# board.net
KiCad netlist of a schematic drawn in EAGLE
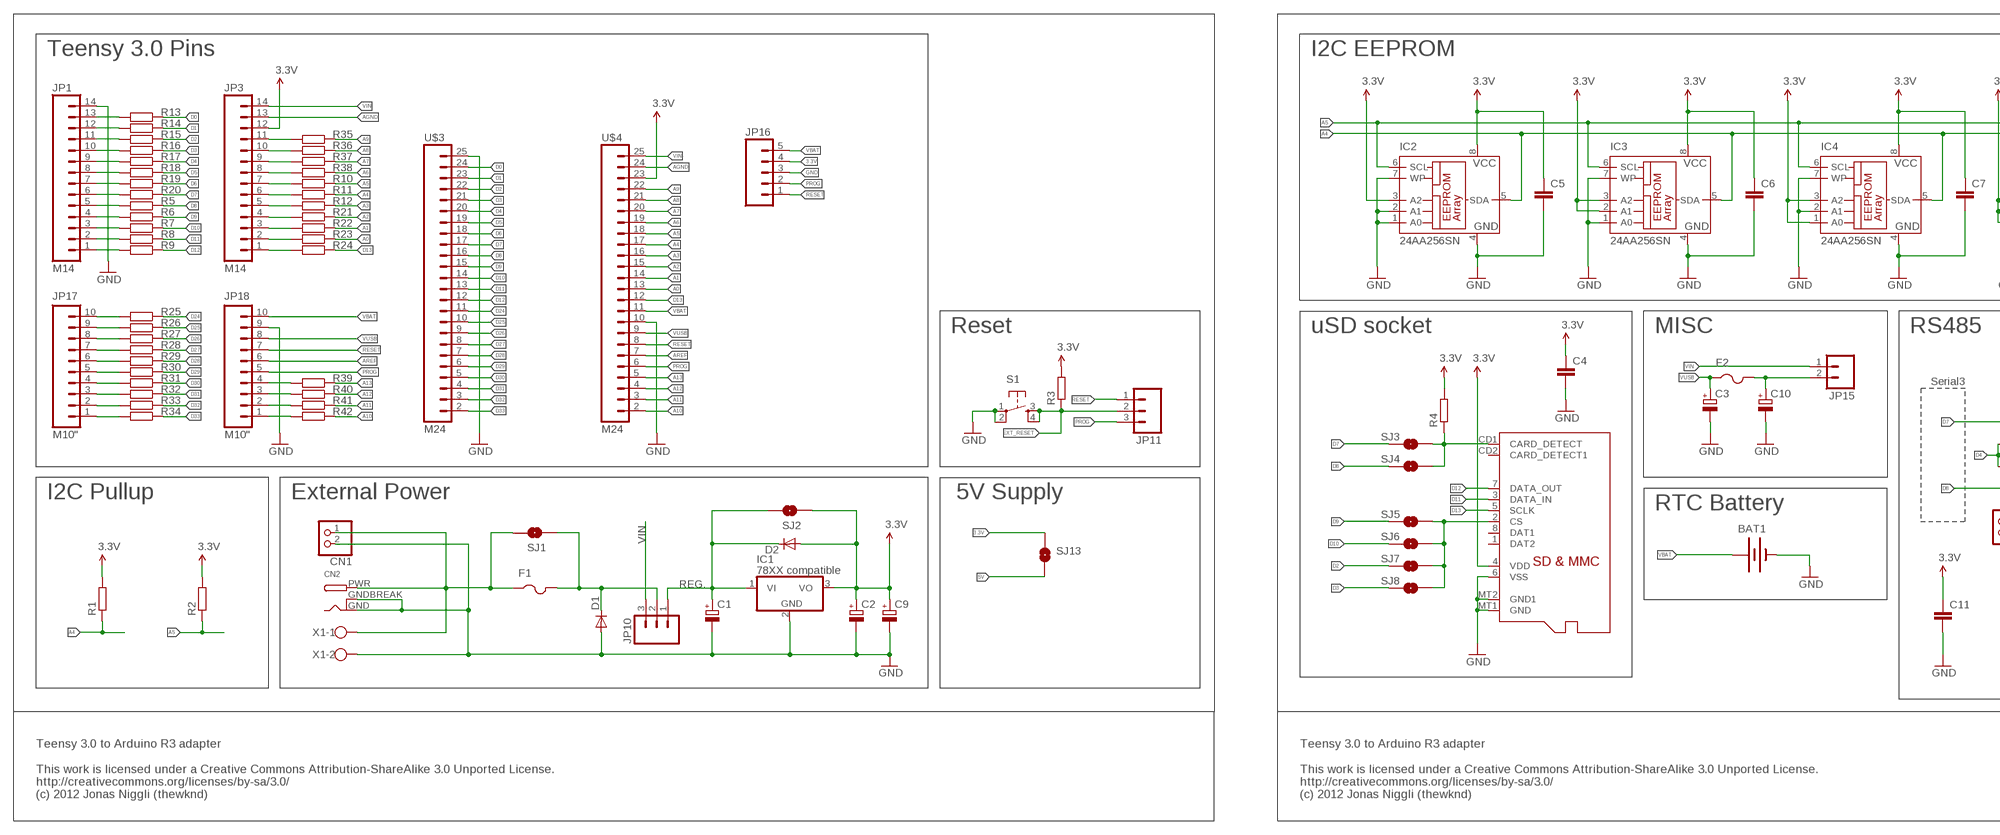
[diagram p0: schematic, sheet 1, part 1 of 2]
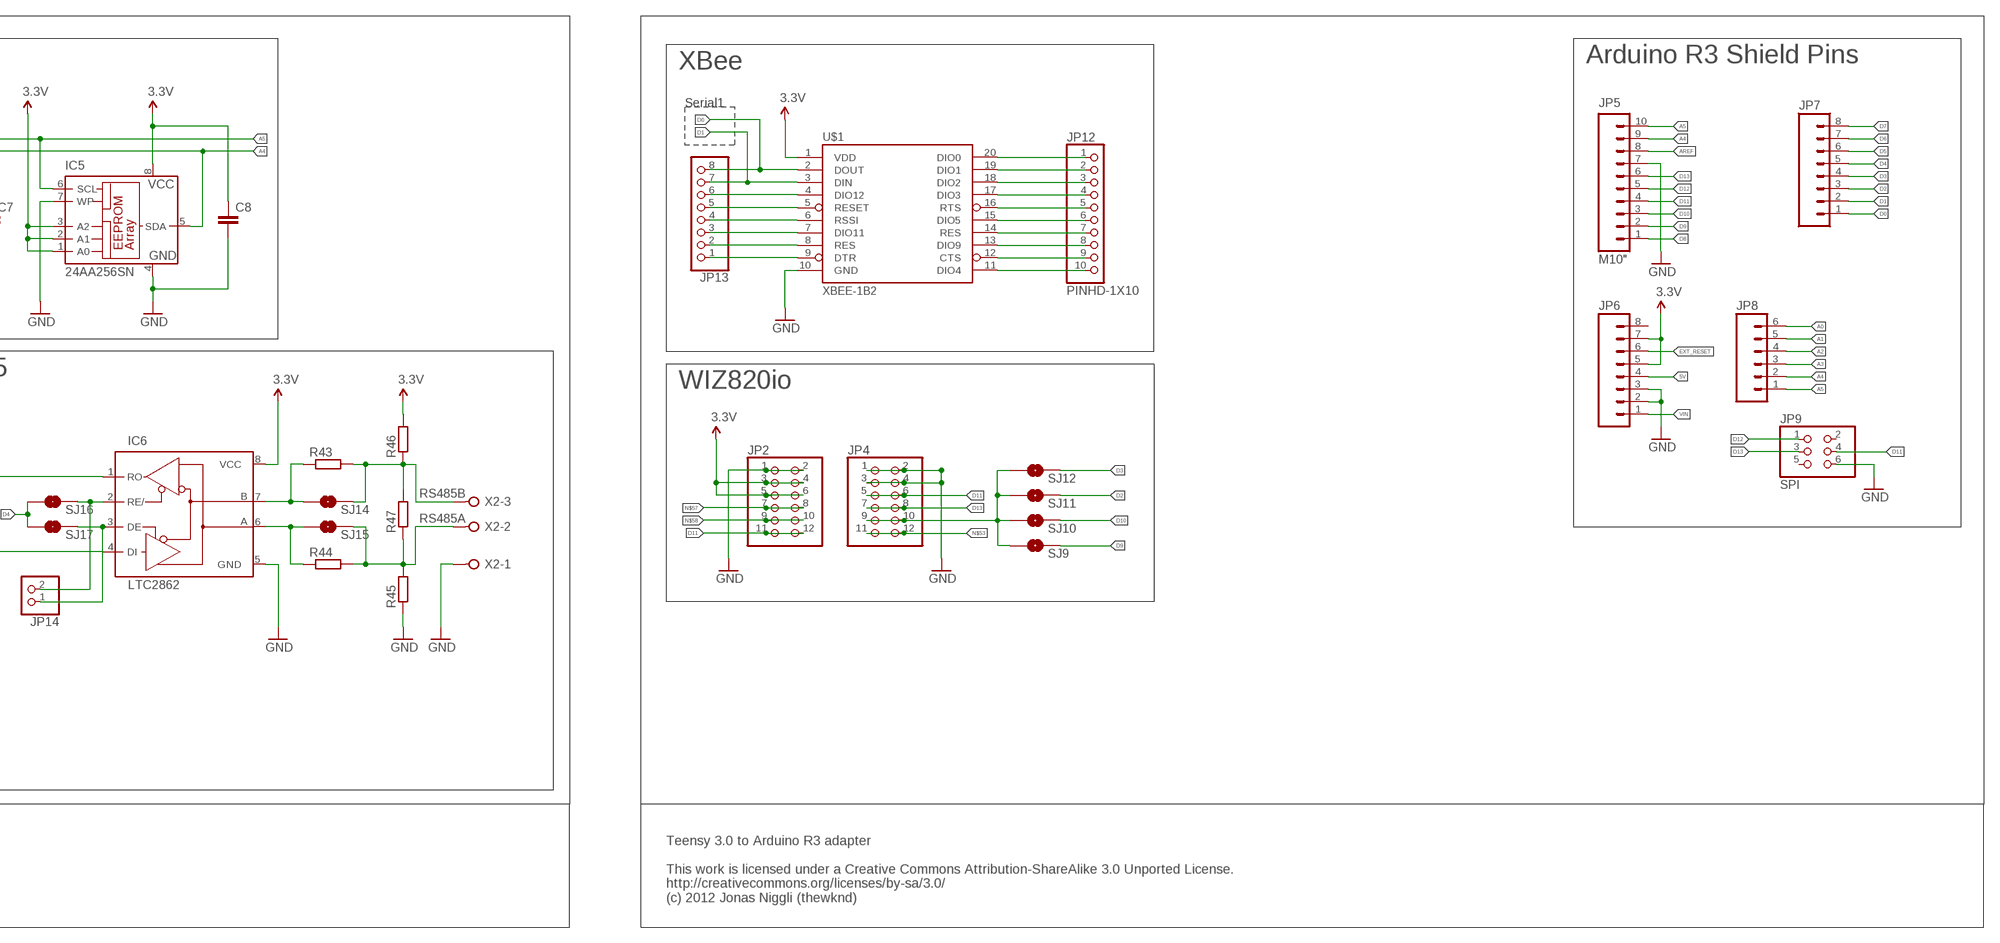
[diagram p1: schematic, sheet 1, part 2 of 2]

(export (version "E")
  (design (tool "Eeschema 10.0.6"))
  (components
    (comp (ref "BAT1")
      (value "BATTERY12MM")
      (footprint "eagle-import:BATTCON_12MM")
      (libsource (lib "eagle-import") (part "BATTERY12MM"))
    )
    (comp (ref "C1")
      (value "CPOL-EUCT3216")
      (footprint "eagle-import:CT3216")
      (libsource (lib "eagle-import") (part "resistor_CPOL-EUCT3216"))
    )
    (comp (ref "C2")
      (value "CPOL-EUCT3216")
      (footprint "eagle-import:CT3216")
      (libsource (lib "eagle-import") (part "resistor_CPOL-EUCT3216"))
    )
    (comp (ref "C3")
      (value "CPOL-EUCT3528")
      (footprint "eagle-import:CT3528")
      (libsource (lib "eagle-import") (part "CPOL-EUCT3528"))
    )
    (comp (ref "C4")
      (value "C-EUC0805K")
      (footprint "eagle-import:C0805K")
      (libsource (lib "eagle-import") (part "C-EUC0805K"))
    )
    (comp (ref "C5")
      (value "C-EUC0805K")
      (footprint "eagle-import:C0805K")
      (libsource (lib "eagle-import") (part "C-EUC0805K"))
    )
    (comp (ref "C6")
      (value "C-EUC0805K")
      (footprint "eagle-import:C0805K")
      (libsource (lib "eagle-import") (part "C-EUC0805K"))
    )
    (comp (ref "C7")
      (value "C-EUC0805K")
      (footprint "eagle-import:C0805K")
      (libsource (lib "eagle-import") (part "C-EUC0805K"))
    )
    (comp (ref "C8")
      (value "C-EUC0805K")
      (footprint "eagle-import:C0805K")
      (libsource (lib "eagle-import") (part "C-EUC0805K"))
    )
    (comp (ref "C9")
      (value "CPOL-EUD")
      (footprint "eagle-import:PANASONIC_D")
      (libsource (lib "eagle-import") (part "resistor_CPOL-EUD"))
    )
    (comp (ref "C10")
      (value "CPOL-EU085CS-1AR")
      (footprint "eagle-import:085CS_1AR")
      (libsource (lib "eagle-import") (part "CPOL-EU085CS-1AR"))
    )
    (comp (ref "C11")
      (value "C-EUC0805K")
      (footprint "eagle-import:C0805K")
      (libsource (lib "eagle-import") (part "C-EUC0805K"))
    )
    (comp (ref "CN1")
      (value "JST_2PIN-THM-RA")
      (footprint "eagle-import:JST-PH-2-THM-RA")
      (libsource (lib "eagle-import") (part "JST_2PIN-THM-RA"))
    )
    (comp (ref "CN2")
      (value "DCBARRELPTH")
      (footprint "eagle-import:DCJACK_2MM_PTH")
      (libsource (lib "eagle-import") (part "DCBARRELPTH"))
    )
    (comp (ref "D1")
      (value "DIODESMA-KIT")
      (footprint "eagle-import:SMA-DIODE-KIT")
      (libsource (lib "eagle-import") (part "DIODESMA-KIT"))
    )
    (comp (ref "D2")
      (value "DIODESMA-KIT")
      (footprint "eagle-import:SMA-DIODE-KIT")
      (libsource (lib "eagle-import") (part "DIODESMA-KIT"))
    )
    (comp (ref "F1")
      (value "PTCFUSE-1812")
      (footprint "eagle-import:1812")
      (libsource (lib "eagle-import") (part "PTCFUSE-1812"))
    )
    (comp (ref "F2")
      (value "PTCFUSE-1812")
      (footprint "eagle-import:1812")
      (libsource (lib "eagle-import") (part "PTCFUSE-1812"))
    )
    (comp (ref "IC1")
      (value "78XX compatible")
      (footprint "eagle-import:TO220V")
      (libsource (lib "eagle-import") (part "78TV05"))
    )
    (comp (ref "IC2")
      (value "24AA256SN")
      (footprint "eagle-import:SO-08")
      (fields (field (name "MPN") "24AA256T-I/SM"))
      (libsource (lib "eagle-import") (part "24SNAA256"))
    )
    (comp (ref "IC3")
      (value "24AA256SN")
      (footprint "eagle-import:SO-08")
      (fields (field (name "MPN") "24AA256T-I/SM"))
      (libsource (lib "eagle-import") (part "24SNAA256"))
    )
    (comp (ref "IC4")
      (value "24AA256SN")
      (footprint "eagle-import:SO-08")
      (fields (field (name "MPN") "24AA256T-I/SM"))
      (libsource (lib "eagle-import") (part "24SNAA256"))
    )
    (comp (ref "IC5")
      (value "24AA256SN")
      (footprint "eagle-import:SO-08")
      (fields (field (name "MPN") "24AA256T-I/SM"))
      (libsource (lib "eagle-import") (part "24SNAA256"))
    )
    (comp (ref "IC6")
      (value "LTC2862")
      (footprint "eagle-import:SO08")
      (fields (field (name "MPN") "MAX3468ESA+T"))
      (libsource (lib "eagle-import") (part "MAX34SA68E"))
    )
    (comp (ref "JP1")
      (value "M14")
      (footprint "eagle-import:1X14")
      (libsource (lib "eagle-import") (part "M14"))
    )
    (comp (ref "JP2")
      (value "PINHD-2X6")
      (footprint "eagle-import:2X06")
      (libsource (lib "eagle-import") (part "PINHD-2X6"))
    )
    (comp (ref "JP3")
      (value "M14")
      (footprint "eagle-import:1X14")
      (libsource (lib "eagle-import") (part "M14"))
    )
    (comp (ref "JP4")
      (value "PINHD-2X6")
      (footprint "eagle-import:2X06")
      (libsource (lib "eagle-import") (part "PINHD-2X6"))
    )
    (comp (ref "JP5")
      (value "M10\"")
      (footprint "eagle-import:1X10")
      (libsource (lib "eagle-import") (part "M10{dblquote}"))
    )
    (comp (ref "JP6")
      (value "M081X08")
      (footprint "eagle-import:1X08")
      (libsource (lib "eagle-import") (part "M081X08"))
    )
    (comp (ref "JP7")
      (value "M081X08")
      (footprint "eagle-import:1X08")
      (libsource (lib "eagle-import") (part "M081X08"))
    )
    (comp (ref "JP8")
      (value "M06SIP")
      (footprint "eagle-import:1X06")
      (libsource (lib "eagle-import") (part "M06SIP"))
    )
    (comp (ref "JP9")
      (value "SPI")
      (footprint "eagle-import:2X03")
      (libsource (lib "eagle-import") (part "PINHD-2X3"))
    )
    (comp (ref "JP10")
      (value "M03PTH")
      (footprint "eagle-import:1X03")
      (libsource (lib "eagle-import") (part "M03PTH"))
    )
    (comp (ref "JP11")
      (value "M03PTH")
      (footprint "eagle-import:1X03")
      (libsource (lib "eagle-import") (part "M03PTH"))
    )
    (comp (ref "JP12")
      (value "PINHD-1X10")
      (footprint "eagle-import:1X10-BIG")
      (libsource (lib "eagle-import") (part "PINHD-1X10"))
    )
    (comp (ref "JP13")
      (value "PINHD-1X8BIG")
      (footprint "eagle-import:1X08-BIG")
      (libsource (lib "eagle-import") (part "PINHD-1X8BIG"))
    )
    (comp (ref "JP14")
      (value "PINHD-1X2")
      (footprint "eagle-import:1X02")
      (libsource (lib "eagle-import") (part "PINHD-1X2"))
    )
    (comp (ref "JP15")
      (value "M02PTH")
      (footprint "eagle-import:1X02")
      (libsource (lib "eagle-import") (part "M02PTH"))
    )
    (comp (ref "JP16")
      (value "M05PTH")
      (footprint "eagle-import:1X05")
      (libsource (lib "eagle-import") (part "M05PTH"))
    )
    (comp (ref "JP17")
      (value "M10\"")
      (footprint "eagle-import:1X10")
      (libsource (lib "eagle-import") (part "M10{dblquote}"))
    )
    (comp (ref "JP18")
      (value "M10\"")
      (footprint "eagle-import:1X10")
      (libsource (lib "eagle-import") (part "M10{dblquote}"))
    )
    (comp (ref "R1")
      (value "R-EU_R0805")
      (footprint "eagle-import:R0805")
      (libsource (lib "eagle-import") (part "R-EU_R0805"))
    )
    (comp (ref "R2")
      (value "R-EU_R0805")
      (footprint "eagle-import:R0805")
      (libsource (lib "eagle-import") (part "R-EU_R0805"))
    )
    (comp (ref "R3")
      (value "R-EU_R0805")
      (footprint "eagle-import:R0805")
      (libsource (lib "eagle-import") (part "R-EU_R0805"))
    )
    (comp (ref "R4")
      (value "R-EU_R0805")
      (footprint "eagle-import:R0805")
      (libsource (lib "eagle-import") (part "R-EU_R0805"))
    )
    (comp (ref "R5")
      (value "R-EU_R0805")
      (footprint "eagle-import:R0805")
      (libsource (lib "eagle-import") (part "R-EU_R0805"))
    )
    (comp (ref "R6")
      (value "R-EU_R0805")
      (footprint "eagle-import:R0805")
      (libsource (lib "eagle-import") (part "R-EU_R0805"))
    )
    (comp (ref "R7")
      (value "R-EU_R0805")
      (footprint "eagle-import:R0805")
      (libsource (lib "eagle-import") (part "R-EU_R0805"))
    )
    (comp (ref "R8")
      (value "R-EU_R0805")
      (footprint "eagle-import:R0805")
      (libsource (lib "eagle-import") (part "R-EU_R0805"))
    )
    (comp (ref "R9")
      (value "R-EU_R0805")
      (footprint "eagle-import:R0805")
      (libsource (lib "eagle-import") (part "R-EU_R0805"))
    )
    (comp (ref "R10")
      (value "R-EU_R0805")
      (footprint "eagle-import:R0805")
      (libsource (lib "eagle-import") (part "R-EU_R0805"))
    )
    (comp (ref "R11")
      (value "R-EU_R0805")
      (footprint "eagle-import:R0805")
      (libsource (lib "eagle-import") (part "R-EU_R0805"))
    )
    (comp (ref "R12")
      (value "R-EU_R0805")
      (footprint "eagle-import:R0805")
      (libsource (lib "eagle-import") (part "R-EU_R0805"))
    )
    (comp (ref "R13")
      (value "R-EU_R0805")
      (footprint "eagle-import:R0805")
      (libsource (lib "eagle-import") (part "R-EU_R0805"))
    )
    (comp (ref "R14")
      (value "R-EU_R0805")
      (footprint "eagle-import:R0805")
      (libsource (lib "eagle-import") (part "R-EU_R0805"))
    )
    (comp (ref "R15")
      (value "R-EU_R0805")
      (footprint "eagle-import:R0805")
      (libsource (lib "eagle-import") (part "R-EU_R0805"))
    )
    (comp (ref "R16")
      (value "R-EU_R0805")
      (footprint "eagle-import:R0805")
      (libsource (lib "eagle-import") (part "R-EU_R0805"))
    )
    (comp (ref "R17")
      (value "R-EU_R0805")
      (footprint "eagle-import:R0805")
      (libsource (lib "eagle-import") (part "R-EU_R0805"))
    )
    (comp (ref "R18")
      (value "R-EU_R0805")
      (footprint "eagle-import:R0805")
      (libsource (lib "eagle-import") (part "R-EU_R0805"))
    )
    (comp (ref "R19")
      (value "R-EU_R0805")
      (footprint "eagle-import:R0805")
      (libsource (lib "eagle-import") (part "R-EU_R0805"))
    )
    (comp (ref "R20")
      (value "R-EU_R0805")
      (footprint "eagle-import:R0805")
      (libsource (lib "eagle-import") (part "R-EU_R0805"))
    )
    (comp (ref "R21")
      (value "R-EU_R0805")
      (footprint "eagle-import:R0805")
      (libsource (lib "eagle-import") (part "R-EU_R0805"))
    )
    (comp (ref "R22")
      (value "R-EU_R0805")
      (footprint "eagle-import:R0805")
      (libsource (lib "eagle-import") (part "R-EU_R0805"))
    )
    (comp (ref "R23")
      (value "R-EU_R0805")
      (footprint "eagle-import:R0805")
      (libsource (lib "eagle-import") (part "R-EU_R0805"))
    )
    (comp (ref "R24")
      (value "R-EU_R0805")
      (footprint "eagle-import:R0805")
      (libsource (lib "eagle-import") (part "R-EU_R0805"))
    )
    (comp (ref "R25")
      (value "R-EU_R0805")
      (footprint "eagle-import:R0805")
      (libsource (lib "eagle-import") (part "R-EU_R0805"))
    )
    (comp (ref "R26")
      (value "R-EU_R0805")
      (footprint "eagle-import:R0805")
      (libsource (lib "eagle-import") (part "R-EU_R0805"))
    )
    (comp (ref "R27")
      (value "R-EU_R0805")
      (footprint "eagle-import:R0805")
      (libsource (lib "eagle-import") (part "R-EU_R0805"))
    )
    (comp (ref "R28")
      (value "R-EU_R0805")
      (footprint "eagle-import:R0805")
      (libsource (lib "eagle-import") (part "R-EU_R0805"))
    )
    (comp (ref "R29")
      (value "R-EU_R0805")
      (footprint "eagle-import:R0805")
      (libsource (lib "eagle-import") (part "R-EU_R0805"))
    )
    (comp (ref "R30")
      (value "R-EU_R0805")
      (footprint "eagle-import:R0805")
      (libsource (lib "eagle-import") (part "R-EU_R0805"))
    )
    (comp (ref "R31")
      (value "R-EU_R0805")
      (footprint "eagle-import:R0805")
      (libsource (lib "eagle-import") (part "R-EU_R0805"))
    )
    (comp (ref "R32")
      (value "R-EU_R0805")
      (footprint "eagle-import:R0805")
      (libsource (lib "eagle-import") (part "R-EU_R0805"))
    )
    (comp (ref "R33")
      (value "R-EU_R0805")
      (footprint "eagle-import:R0805")
      (libsource (lib "eagle-import") (part "R-EU_R0805"))
    )
    (comp (ref "R34")
      (value "R-EU_R0805")
      (footprint "eagle-import:R0805")
      (libsource (lib "eagle-import") (part "R-EU_R0805"))
    )
    (comp (ref "R35")
      (value "R-EU_R0805")
      (footprint "eagle-import:R0805")
      (libsource (lib "eagle-import") (part "R-EU_R0805"))
    )
    (comp (ref "R36")
      (value "R-EU_R0805")
      (footprint "eagle-import:R0805")
      (libsource (lib "eagle-import") (part "R-EU_R0805"))
    )
    (comp (ref "R37")
      (value "R-EU_R0805")
      (footprint "eagle-import:R0805")
      (libsource (lib "eagle-import") (part "R-EU_R0805"))
    )
    (comp (ref "R38")
      (value "R-EU_R0805")
      (footprint "eagle-import:R0805")
      (libsource (lib "eagle-import") (part "R-EU_R0805"))
    )
    (comp (ref "R39")
      (value "R-EU_R0805")
      (footprint "eagle-import:R0805")
      (libsource (lib "eagle-import") (part "R-EU_R0805"))
    )
    (comp (ref "R40")
      (value "R-EU_R0805")
      (footprint "eagle-import:R0805")
      (libsource (lib "eagle-import") (part "R-EU_R0805"))
    )
    (comp (ref "R41")
      (value "R-EU_R0805")
      (footprint "eagle-import:R0805")
      (libsource (lib "eagle-import") (part "R-EU_R0805"))
    )
    (comp (ref "R42")
      (value "R-EU_R0805")
      (footprint "eagle-import:R0805")
      (libsource (lib "eagle-import") (part "R-EU_R0805"))
    )
    (comp (ref "R43")
      (value "R-EU_R0805")
      (footprint "eagle-import:R0805")
      (libsource (lib "eagle-import") (part "R-EU_R0805"))
    )
    (comp (ref "R44")
      (value "R-EU_R0805")
      (footprint "eagle-import:R0805")
      (libsource (lib "eagle-import") (part "R-EU_R0805"))
    )
    (comp (ref "R45")
      (value "R-EU_R0805")
      (footprint "eagle-import:R0805")
      (libsource (lib "eagle-import") (part "R-EU_R0805"))
    )
    (comp (ref "R46")
      (value "R-EU_R0805")
      (footprint "eagle-import:R0805")
      (libsource (lib "eagle-import") (part "R-EU_R0805"))
    )
    (comp (ref "R47")
      (value "R-EU_R0805")
      (footprint "eagle-import:R0805")
      (libsource (lib "eagle-import") (part "R-EU_R0805"))
    )
    (comp (ref "S1")
      (value "TAC_SWITCHPTH")
      (footprint "eagle-import:TACTILE-PTH")
      (libsource (lib "eagle-import") (part "TAC_SWITCHPTH"))
    )
    (comp (ref "SJ1")
      (value "SOLDERJUMPERNO")
      (footprint "eagle-import:SJ_2S-NO")
      (libsource (lib "eagle-import") (part "SOLDERJUMPERNO"))
    )
    (comp (ref "SJ2")
      (value "SOLDERJUMPERNO")
      (footprint "eagle-import:SJ_2S-NO")
      (libsource (lib "eagle-import") (part "SOLDERJUMPERNO"))
    )
    (comp (ref "SJ3")
      (value "SOLDERJUMPERNO")
      (footprint "eagle-import:SJ_2S-NO")
      (libsource (lib "eagle-import") (part "SOLDERJUMPERNO"))
    )
    (comp (ref "SJ4")
      (value "SOLDERJUMPERNO")
      (footprint "eagle-import:SJ_2S-NO")
      (libsource (lib "eagle-import") (part "SOLDERJUMPERNO"))
    )
    (comp (ref "SJ5")
      (value "SOLDERJUMPERNO")
      (footprint "eagle-import:SJ_2S-NO")
      (libsource (lib "eagle-import") (part "SOLDERJUMPERNO"))
    )
    (comp (ref "SJ6")
      (value "SOLDERJUMPERNO")
      (footprint "eagle-import:SJ_2S-NO")
      (libsource (lib "eagle-import") (part "SOLDERJUMPERNO"))
    )
    (comp (ref "SJ7")
      (value "SOLDERJUMPERNO")
      (footprint "eagle-import:SJ_2S-NO")
      (libsource (lib "eagle-import") (part "SOLDERJUMPERNO"))
    )
    (comp (ref "SJ8")
      (value "SOLDERJUMPERNO")
      (footprint "eagle-import:SJ_2S-NO")
      (libsource (lib "eagle-import") (part "SOLDERJUMPERNO"))
    )
    (comp (ref "SJ9")
      (value "SOLDERJUMPERNO")
      (footprint "eagle-import:SJ_2S-NO")
      (libsource (lib "eagle-import") (part "SOLDERJUMPERNO"))
    )
    (comp (ref "SJ10")
      (value "SOLDERJUMPERNO")
      (footprint "eagle-import:SJ_2S-NO")
      (libsource (lib "eagle-import") (part "SOLDERJUMPERNO"))
    )
    (comp (ref "SJ11")
      (value "SOLDERJUMPERNO")
      (footprint "eagle-import:SJ_2S-NO")
      (libsource (lib "eagle-import") (part "SOLDERJUMPERNO"))
    )
    (comp (ref "SJ12")
      (value "SOLDERJUMPERNO")
      (footprint "eagle-import:SJ_2S-NO")
      (libsource (lib "eagle-import") (part "SOLDERJUMPERNO"))
    )
    (comp (ref "SJ13")
      (value "SOLDERJUMPERNO")
      (footprint "eagle-import:SJ_2S-NO")
      (libsource (lib "eagle-import") (part "SOLDERJUMPERNO"))
    )
    (comp (ref "SJ14")
      (value "SOLDERJUMPERNO")
      (footprint "eagle-import:SJ_2S-NO")
      (libsource (lib "eagle-import") (part "SOLDERJUMPERNO"))
    )
    (comp (ref "SJ15")
      (value "SOLDERJUMPERNO")
      (footprint "eagle-import:SJ_2S-NO")
      (libsource (lib "eagle-import") (part "SOLDERJUMPERNO"))
    )
    (comp (ref "SJ16")
      (value "SOLDERJUMPERNO")
      (footprint "eagle-import:SJ_2S-NO")
      (libsource (lib "eagle-import") (part "SOLDERJUMPERNO"))
    )
    (comp (ref "SJ17")
      (value "SOLDERJUMPERNO")
      (footprint "eagle-import:SJ_2S-NO")
      (libsource (lib "eagle-import") (part "SOLDERJUMPERNO"))
    )
    (comp (ref "U$1")
      (value "XBEE-1B2")
      (footprint "eagle-import:XBEE-SILK")
      (libsource (lib "eagle-import") (part "XBEE-1B2"))
    )
    (comp (ref "U$3")
      (value "M24")
      (footprint "eagle-import:1X24")
      (libsource (lib "eagle-import") (part "M24"))
    )
    (comp (ref "U$4")
      (value "M24")
      (footprint "eagle-import:1X24")
      (libsource (lib "eagle-import") (part "M24"))
    )
    (comp (ref "U1")
      (value "MICROSD")
      (footprint "eagle-import:MICROSD")
      (libsource (lib "eagle-import") (part "MICROSD"))
    )
    (comp (ref "X1")
      (value "W237-102")
      (footprint "eagle-import:W237-102")
      (fields (field (name "MPN") "237-102"))
      (libsource (lib "eagle-import") (part "W237-102"))
    )
    (comp (ref "X2")
      (value "W237-03P")
      (footprint "eagle-import:W237-133")
      (fields (field (name "OC_NEWARK") "unknown"))
      (libsource (lib "eagle-import") (part "W237-03P"))
    )
  )
  (nets
    (net (code "1") (name "3.3V") (class "Default")
      (node (ref "C11") (pin "1") (pinfunction "1_1") (pintype "passive"))
      (node (ref "C2") (pin "+") (pinfunction "+_+") (pintype "passive"))
      (node (ref "C4") (pin "1") (pinfunction "1_1") (pintype "passive"))
      (node (ref "C5") (pin "1") (pinfunction "1_1") (pintype "passive"))
      (node (ref "C6") (pin "1") (pinfunction "1_1") (pintype "passive"))
      (node (ref "C7") (pin "1") (pinfunction "1_1") (pintype "passive"))
      (node (ref "C8") (pin "1") (pinfunction "1_1") (pintype "passive"))
      (node (ref "C9") (pin "+") (pinfunction "+_+") (pintype "passive"))
      (node (ref "D2") (pin "A") (pinfunction "A_A") (pintype "passive"))
      (node (ref "IC1") (pin "3") (pinfunction "VO_3") (pintype "passive"))
      (node (ref "IC2") (pin "3") (pinfunction "A2_3") (pintype "input"))
      (node (ref "IC2") (pin "8") (pinfunction "VCC_8") (pintype "power_in"))
      (node (ref "IC3") (pin "2") (pinfunction "A1_2") (pintype "input"))
      (node (ref "IC3") (pin "3") (pinfunction "A2_3") (pintype "input"))
      (node (ref "IC3") (pin "8") (pinfunction "VCC_8") (pintype "power_in"))
      (node (ref "IC4") (pin "1") (pinfunction "A0_1") (pintype "input"))
      (node (ref "IC4") (pin "3") (pinfunction "A2_3") (pintype "input"))
      (node (ref "IC4") (pin "8") (pinfunction "VCC_8") (pintype "power_in"))
      (node (ref "IC5") (pin "1") (pinfunction "A0_1") (pintype "input"))
      (node (ref "IC5") (pin "2") (pinfunction "A1_2") (pintype "input"))
      (node (ref "IC5") (pin "3") (pinfunction "A2_3") (pintype "input"))
      (node (ref "IC5") (pin "8") (pinfunction "VCC_8") (pintype "power_in"))
      (node (ref "IC6") (pin "8") (pinfunction "VCC_8") (pintype "power_in"))
      (node (ref "JP16") (pin "4") (pinfunction "4_4") (pintype "passive"))
      (node (ref "JP2") (pin "3") (pinfunction "3_3") (pintype "passive"))
      (node (ref "JP2") (pin "4") (pinfunction "4_4") (pintype "passive"))
      (node (ref "JP2") (pin "5") (pinfunction "5_5") (pintype "passive"))
      (node (ref "JP2") (pin "6") (pinfunction "6_6") (pintype "passive"))
      (node (ref "JP3") (pin "12") (pinfunction "12_12") (pintype "passive"))
      (node (ref "JP6") (pin "5") (pinfunction "5_5") (pintype "passive"))
      (node (ref "JP6") (pin "7") (pinfunction "7_7") (pintype "passive"))
      (node (ref "R1") (pin "2") (pinfunction "2_2") (pintype "passive"))
      (node (ref "R2") (pin "2") (pinfunction "2_2") (pintype "passive"))
      (node (ref "R3") (pin "2") (pinfunction "2_2") (pintype "passive"))
      (node (ref "R4") (pin "2") (pinfunction "2_2") (pintype "passive"))
      (node (ref "R46") (pin "2") (pinfunction "2_2") (pintype "passive"))
      (node (ref "SJ13") (pin "1") (pinfunction "1_1") (pintype "passive"))
      (node (ref "SJ2") (pin "1") (pinfunction "1_1") (pintype "passive"))
      (node (ref "U$1") (pin "1") (pinfunction "VDD_1") (pintype "power_in"))
      (node (ref "U$4") (pin "23") (pinfunction "23_23") (pintype "passive"))
      (node (ref "U1") (pin "4") (pinfunction "VDD_4") (pintype "power_in"))
    )
    (net (code "2") (name "5V") (class "Default")
      (node (ref "JP6") (pin "4") (pinfunction "4_4") (pintype "passive"))
      (node (ref "SJ13") (pin "2") (pinfunction "2_2") (pintype "passive"))
    )
    (net (code "3") (name "A0") (class "Default")
      (node (ref "JP8") (pin "6") (pinfunction "6_6") (pintype "passive"))
      (node (ref "R23") (pin "1") (pinfunction "1_1") (pintype "passive"))
      (node (ref "U$4") (pin "13") (pinfunction "13_13") (pintype "passive"))
    )
    (net (code "4") (name "A1") (class "Default")
      (node (ref "JP8") (pin "5") (pinfunction "5_5") (pintype "passive"))
      (node (ref "R22") (pin "1") (pinfunction "1_1") (pintype "passive"))
      (node (ref "U$4") (pin "14") (pinfunction "14_14") (pintype "passive"))
    )
    (net (code "5") (name "A2") (class "Default")
      (node (ref "JP8") (pin "4") (pinfunction "4_4") (pintype "passive"))
      (node (ref "R21") (pin "1") (pinfunction "1_1") (pintype "passive"))
      (node (ref "U$4") (pin "15") (pinfunction "15_15") (pintype "passive"))
    )
    (net (code "6") (name "A3") (class "Default")
      (node (ref "JP8") (pin "3") (pinfunction "3_3") (pintype "passive"))
      (node (ref "R12") (pin "1") (pinfunction "1_1") (pintype "passive"))
      (node (ref "U$4") (pin "16") (pinfunction "16_16") (pintype "passive"))
    )
    (net (code "7") (name "A4") (class "Default")
      (node (ref "IC2") (pin "5") (pinfunction "SDA_5") (pintype "bidirectional"))
      (node (ref "IC3") (pin "5") (pinfunction "SDA_5") (pintype "bidirectional"))
      (node (ref "IC4") (pin "5") (pinfunction "SDA_5") (pintype "bidirectional"))
      (node (ref "IC5") (pin "5") (pinfunction "SDA_5") (pintype "bidirectional"))
      (node (ref "JP5") (pin "9") (pinfunction "9_9") (pintype "passive"))
      (node (ref "JP8") (pin "2") (pinfunction "2_2") (pintype "passive"))
      (node (ref "R1") (pin "1") (pinfunction "1_1") (pintype "passive"))
      (node (ref "R11") (pin "1") (pinfunction "1_1") (pintype "passive"))
      (node (ref "U$4") (pin "17") (pinfunction "17_17") (pintype "passive"))
    )
    (net (code "8") (name "A5") (class "Default")
      (node (ref "IC2") (pin "6") (pinfunction "SCL_6") (pintype "input"))
      (node (ref "IC3") (pin "6") (pinfunction "SCL_6") (pintype "input"))
      (node (ref "IC4") (pin "6") (pinfunction "SCL_6") (pintype "input"))
      (node (ref "IC5") (pin "6") (pinfunction "SCL_6") (pintype "input"))
      (node (ref "JP5") (pin "10") (pinfunction "10_10") (pintype "passive"))
      (node (ref "JP8") (pin "1") (pinfunction "1_1") (pintype "passive"))
      (node (ref "R10") (pin "1") (pinfunction "1_1") (pintype "passive"))
      (node (ref "R2") (pin "1") (pinfunction "1_1") (pintype "passive"))
      (node (ref "U$4") (pin "18") (pinfunction "18_18") (pintype "passive"))
    )
    (net (code "9") (name "A6") (class "Default")
      (node (ref "R38") (pin "1") (pinfunction "1_1") (pintype "passive"))
      (node (ref "U$4") (pin "19") (pinfunction "19_19") (pintype "passive"))
    )
    (net (code "10") (name "A7") (class "Default")
      (node (ref "R37") (pin "1") (pinfunction "1_1") (pintype "passive"))
      (node (ref "U$4") (pin "20") (pinfunction "20_20") (pintype "passive"))
    )
    (net (code "11") (name "A8") (class "Default")
      (node (ref "R36") (pin "1") (pinfunction "1_1") (pintype "passive"))
      (node (ref "U$4") (pin "21") (pinfunction "21_21") (pintype "passive"))
    )
    (net (code "12") (name "A9") (class "Default")
      (node (ref "R35") (pin "1") (pinfunction "1_1") (pintype "passive"))
      (node (ref "U$4") (pin "22") (pinfunction "22_22") (pintype "passive"))
    )
    (net (code "13") (name "A10") (class "Default")
      (node (ref "R42") (pin "1") (pinfunction "1_1") (pintype "passive"))
      (node (ref "U$4") (pin "2") (pinfunction "2_2") (pintype "passive"))
    )
    (net (code "14") (name "A11") (class "Default")
      (node (ref "R41") (pin "1") (pinfunction "1_1") (pintype "passive"))
      (node (ref "U$4") (pin "3") (pinfunction "3_3") (pintype "passive"))
    )
    (net (code "15") (name "A12") (class "Default")
      (node (ref "R40") (pin "1") (pinfunction "1_1") (pintype "passive"))
      (node (ref "U$4") (pin "4") (pinfunction "4_4") (pintype "passive"))
    )
    (net (code "16") (name "A13") (class "Default")
      (node (ref "R39") (pin "1") (pinfunction "1_1") (pintype "passive"))
      (node (ref "U$4") (pin "5") (pinfunction "5_5") (pintype "passive"))
    )
    (net (code "17") (name "AGND") (class "Default")
      (node (ref "JP3") (pin "13") (pinfunction "13_13") (pintype "passive"))
      (node (ref "U$4") (pin "24") (pinfunction "24_24") (pintype "passive"))
    )
    (net (code "18") (name "AREF") (class "Default")
      (node (ref "JP18") (pin "6") (pinfunction "6_6") (pintype "passive"))
      (node (ref "JP5") (pin "8") (pinfunction "8_8") (pintype "passive"))
      (node (ref "U$4") (pin "7") (pinfunction "7_7") (pintype "passive"))
    )
    (net (code "19") (name "D0") (class "Default")
      (node (ref "JP13") (pin "8") (pinfunction "8_8") (pintype "passive"))
      (node (ref "JP7") (pin "1") (pinfunction "1_1") (pintype "passive"))
      (node (ref "R13") (pin "1") (pinfunction "1_1") (pintype "passive"))
      (node (ref "U$1") (pin "2") (pinfunction "DOUT_2") (pintype "output"))
      (node (ref "U$3") (pin "24") (pinfunction "24_24") (pintype "passive"))
    )
    (net (code "20") (name "D1") (class "Default")
      (node (ref "JP13") (pin "7") (pinfunction "7_7") (pintype "passive"))
      (node (ref "JP7") (pin "2") (pinfunction "2_2") (pintype "passive"))
      (node (ref "R14") (pin "1") (pinfunction "1_1") (pintype "passive"))
      (node (ref "U$1") (pin "3") (pinfunction "DIN_3") (pintype "input"))
      (node (ref "U$3") (pin "23") (pinfunction "23_23") (pintype "passive"))
    )
    (net (code "21") (name "D2") (class "Default")
      (node (ref "JP7") (pin "3") (pinfunction "3_3") (pintype "passive"))
      (node (ref "R15") (pin "1") (pinfunction "1_1") (pintype "passive"))
      (node (ref "SJ11") (pin "2") (pinfunction "2_2") (pintype "passive"))
      (node (ref "SJ7") (pin "2") (pinfunction "2_2") (pintype "passive"))
      (node (ref "U$3") (pin "22") (pinfunction "22_22") (pintype "passive"))
    )
    (net (code "22") (name "D3") (class "Default")
      (node (ref "JP7") (pin "4") (pinfunction "4_4") (pintype "passive"))
      (node (ref "R16") (pin "1") (pinfunction "1_1") (pintype "passive"))
      (node (ref "SJ12") (pin "2") (pinfunction "2_2") (pintype "passive"))
      (node (ref "SJ8") (pin "2") (pinfunction "2_2") (pintype "passive"))
      (node (ref "U$3") (pin "21") (pinfunction "21_21") (pintype "passive"))
    )
    (net (code "23") (name "D4") (class "Default")
      (node (ref "JP7") (pin "5") (pinfunction "5_5") (pintype "passive"))
      (node (ref "R17") (pin "1") (pinfunction "1_1") (pintype "passive"))
      (node (ref "SJ16") (pin "1") (pinfunction "1_1") (pintype "passive"))
      (node (ref "SJ17") (pin "1") (pinfunction "1_1") (pintype "passive"))
      (node (ref "U$3") (pin "20") (pinfunction "20_20") (pintype "passive"))
    )
    (net (code "24") (name "D5") (class "Default")
      (node (ref "JP7") (pin "6") (pinfunction "6_6") (pintype "passive"))
      (node (ref "R18") (pin "1") (pinfunction "1_1") (pintype "passive"))
      (node (ref "U$3") (pin "19") (pinfunction "19_19") (pintype "passive"))
    )
    (net (code "25") (name "D6") (class "Default")
      (node (ref "JP7") (pin "7") (pinfunction "7_7") (pintype "passive"))
      (node (ref "R19") (pin "1") (pinfunction "1_1") (pintype "passive"))
      (node (ref "U$3") (pin "18") (pinfunction "18_18") (pintype "passive"))
    )
    (net (code "26") (name "D7") (class "Default")
      (node (ref "IC6") (pin "1") (pinfunction "RO_1") (pintype "output"))
      (node (ref "JP7") (pin "8") (pinfunction "8_8") (pintype "passive"))
      (node (ref "R20") (pin "1") (pinfunction "1_1") (pintype "passive"))
      (node (ref "SJ3") (pin "2") (pinfunction "2_2") (pintype "passive"))
      (node (ref "U$3") (pin "17") (pinfunction "17_17") (pintype "passive"))
    )
    (net (code "27") (name "D8") (class "Default")
      (node (ref "IC6") (pin "4") (pinfunction "DI_4") (pintype "input"))
      (node (ref "JP5") (pin "1") (pinfunction "1_1") (pintype "passive"))
      (node (ref "R5") (pin "1") (pinfunction "1_1") (pintype "passive"))
      (node (ref "SJ4") (pin "2") (pinfunction "2_2") (pintype "passive"))
      (node (ref "U$3") (pin "16") (pinfunction "16_16") (pintype "passive"))
    )
    (net (code "28") (name "D9") (class "Default")
      (node (ref "JP5") (pin "2") (pinfunction "2_2") (pintype "passive"))
      (node (ref "R6") (pin "1") (pinfunction "1_1") (pintype "passive"))
      (node (ref "SJ5") (pin "2") (pinfunction "2_2") (pintype "passive"))
      (node (ref "SJ9") (pin "2") (pinfunction "2_2") (pintype "passive"))
      (node (ref "U$3") (pin "15") (pinfunction "15_15") (pintype "passive"))
    )
    (net (code "29") (name "D10") (class "Default")
      (node (ref "JP5") (pin "3") (pinfunction "3_3") (pintype "passive"))
      (node (ref "R7") (pin "1") (pinfunction "1_1") (pintype "passive"))
      (node (ref "SJ10") (pin "2") (pinfunction "2_2") (pintype "passive"))
      (node (ref "SJ6") (pin "2") (pinfunction "2_2") (pintype "passive"))
      (node (ref "U$3") (pin "14") (pinfunction "14_14") (pintype "passive"))
    )
    (net (code "30") (name "D11") (class "Default")
      (node (ref "JP2") (pin "11") (pinfunction "11_11") (pintype "passive"))
      (node (ref "JP2") (pin "12") (pinfunction "12_12") (pintype "passive"))
      (node (ref "JP4") (pin "5") (pinfunction "5_5") (pintype "passive"))
      (node (ref "JP4") (pin "6") (pinfunction "6_6") (pintype "passive"))
      (node (ref "JP5") (pin "4") (pinfunction "4_4") (pintype "passive"))
      (node (ref "JP9") (pin "4") (pinfunction "4_4") (pintype "passive"))
      (node (ref "R8") (pin "1") (pinfunction "1_1") (pintype "passive"))
      (node (ref "U$3") (pin "13") (pinfunction "13_13") (pintype "passive"))
      (node (ref "U1") (pin "3") (pinfunction "DATA_IN_3") (pintype "input"))
    )
    (net (code "31") (name "D12") (class "Default")
      (node (ref "JP5") (pin "5") (pinfunction "5_5") (pintype "passive"))
      (node (ref "JP9") (pin "1") (pinfunction "1_1") (pintype "passive"))
      (node (ref "R9") (pin "1") (pinfunction "1_1") (pintype "passive"))
      (node (ref "U$3") (pin "12") (pinfunction "12_12") (pintype "passive"))
      (node (ref "U1") (pin "7") (pinfunction "DATA_OUT_7") (pintype "output"))
    )
    (net (code "32") (name "D13") (class "Default")
      (node (ref "JP4") (pin "7") (pinfunction "7_7") (pintype "passive"))
      (node (ref "JP4") (pin "8") (pinfunction "8_8") (pintype "passive"))
      (node (ref "JP5") (pin "6") (pinfunction "6_6") (pintype "passive"))
      (node (ref "JP9") (pin "3") (pinfunction "3_3") (pintype "passive"))
      (node (ref "R24") (pin "1") (pinfunction "1_1") (pintype "passive"))
      (node (ref "U$4") (pin "12") (pinfunction "12_12") (pintype "passive"))
      (node (ref "U1") (pin "5") (pinfunction "SCLK_5") (pintype "input"))
    )
    (net (code "33") (name "D24") (class "Default")
      (node (ref "R25") (pin "1") (pinfunction "1_1") (pintype "passive"))
      (node (ref "U$3") (pin "11") (pinfunction "11_11") (pintype "passive"))
    )
    (net (code "34") (name "D25") (class "Default")
      (node (ref "R26") (pin "1") (pinfunction "1_1") (pintype "passive"))
      (node (ref "U$3") (pin "10") (pinfunction "10_10") (pintype "passive"))
    )
    (net (code "35") (name "D26") (class "Default")
      (node (ref "R27") (pin "1") (pinfunction "1_1") (pintype "passive"))
      (node (ref "U$3") (pin "9") (pinfunction "9_9") (pintype "passive"))
    )
    (net (code "36") (name "D27") (class "Default")
      (node (ref "R28") (pin "1") (pinfunction "1_1") (pintype "passive"))
      (node (ref "U$3") (pin "8") (pinfunction "8_8") (pintype "passive"))
    )
    (net (code "37") (name "D28") (class "Default")
      (node (ref "R29") (pin "1") (pinfunction "1_1") (pintype "passive"))
      (node (ref "U$3") (pin "7") (pinfunction "7_7") (pintype "passive"))
    )
    (net (code "38") (name "D29") (class "Default")
      (node (ref "R30") (pin "1") (pinfunction "1_1") (pintype "passive"))
      (node (ref "U$3") (pin "6") (pinfunction "6_6") (pintype "passive"))
    )
    (net (code "39") (name "D30") (class "Default")
      (node (ref "R31") (pin "1") (pinfunction "1_1") (pintype "passive"))
      (node (ref "U$3") (pin "5") (pinfunction "5_5") (pintype "passive"))
    )
    (net (code "40") (name "D31") (class "Default")
      (node (ref "R32") (pin "1") (pinfunction "1_1") (pintype "passive"))
      (node (ref "U$3") (pin "4") (pinfunction "4_4") (pintype "passive"))
    )
    (net (code "41") (name "D32") (class "Default")
      (node (ref "R33") (pin "1") (pinfunction "1_1") (pintype "passive"))
      (node (ref "U$3") (pin "3") (pinfunction "3_3") (pintype "passive"))
    )
    (net (code "42") (name "D33") (class "Default")
      (node (ref "R34") (pin "1") (pinfunction "1_1") (pintype "passive"))
      (node (ref "U$3") (pin "2") (pinfunction "2_2") (pintype "passive"))
    )
    (net (code "43") (name "EXT_RESET") (class "Default")
      (node (ref "JP11") (pin "2") (pinfunction "2_2") (pintype "passive"))
      (node (ref "JP6") (pin "6") (pinfunction "6_6") (pintype "passive"))
      (node (ref "R3") (pin "1") (pinfunction "1_1") (pintype "passive"))
      (node (ref "S1") (pin "3") (pinfunction "3_3") (pintype "passive"))
      (node (ref "S1") (pin "4") (pinfunction "4_4") (pintype "passive"))
    )
    (net (code "44") (name "GND") (class "Default")
      (node (ref "BAT1") (pin "GND") (pinfunction "-_GND") (pintype "power_in"))
      (node (ref "C1") (pin "-") (pinfunction "-_-") (pintype "passive"))
      (node (ref "C10") (pin "-") (pinfunction "-_-") (pintype "passive"))
      (node (ref "C11") (pin "2") (pinfunction "2_2") (pintype "passive"))
      (node (ref "C2") (pin "-") (pinfunction "-_-") (pintype "passive"))
      (node (ref "C3") (pin "-") (pinfunction "-_-") (pintype "passive"))
      (node (ref "C4") (pin "2") (pinfunction "2_2") (pintype "passive"))
      (node (ref "C5") (pin "2") (pinfunction "2_2") (pintype "passive"))
      (node (ref "C6") (pin "2") (pinfunction "2_2") (pintype "passive"))
      (node (ref "C7") (pin "2") (pinfunction "2_2") (pintype "passive"))
      (node (ref "C8") (pin "2") (pinfunction "2_2") (pintype "passive"))
      (node (ref "C9") (pin "-") (pinfunction "-_-") (pintype "passive"))
      (node (ref "CN1") (pin "2") (pinfunction "1_2") (pintype "passive"))
      (node (ref "CN2") (pin "GND") (pinfunction "GND_GND") (pintype "power_in"))
      (node (ref "CN2") (pin "GNDBREAK") (pinfunction "GNDBREAK_GNDBREAK") (pintype "power_in"))
      (node (ref "D1") (pin "A") (pinfunction "A_A") (pintype "passive"))
      (node (ref "IC1") (pin "2") (pinfunction "GND_2") (pintype "passive"))
      (node (ref "IC2") (pin "1") (pinfunction "A0_1") (pintype "input"))
      (node (ref "IC2") (pin "2") (pinfunction "A1_2") (pintype "input"))
      (node (ref "IC2") (pin "4") (pinfunction "GND_4") (pintype "power_in"))
      (node (ref "IC2") (pin "7") (pinfunction "WP_7") (pintype "input"))
      (node (ref "IC3") (pin "1") (pinfunction "A0_1") (pintype "input"))
      (node (ref "IC3") (pin "4") (pinfunction "GND_4") (pintype "power_in"))
      (node (ref "IC3") (pin "7") (pinfunction "WP_7") (pintype "input"))
      (node (ref "IC4") (pin "2") (pinfunction "A1_2") (pintype "input"))
      (node (ref "IC4") (pin "4") (pinfunction "GND_4") (pintype "power_in"))
      (node (ref "IC4") (pin "7") (pinfunction "WP_7") (pintype "input"))
      (node (ref "IC5") (pin "4") (pinfunction "GND_4") (pintype "power_in"))
      (node (ref "IC5") (pin "7") (pinfunction "WP_7") (pintype "input"))
      (node (ref "IC6") (pin "5") (pinfunction "GND_5") (pintype "power_in"))
      (node (ref "JP1") (pin "14") (pinfunction "14_14") (pintype "passive"))
      (node (ref "JP16") (pin "3") (pinfunction "3_3") (pintype "passive"))
      (node (ref "JP18") (pin "9") (pinfunction "9_9") (pintype "passive"))
      (node (ref "JP2") (pin "1") (pinfunction "1_1") (pintype "passive"))
      (node (ref "JP2") (pin "2") (pinfunction "2_2") (pintype "passive"))
      (node (ref "JP4") (pin "1") (pinfunction "1_1") (pintype "passive"))
      (node (ref "JP4") (pin "2") (pinfunction "2_2") (pintype "passive"))
      (node (ref "JP4") (pin "3") (pinfunction "3_3") (pintype "passive"))
      (node (ref "JP4") (pin "4") (pinfunction "4_4") (pintype "passive"))
      (node (ref "JP5") (pin "7") (pinfunction "7_7") (pintype "passive"))
      (node (ref "JP6") (pin "2") (pinfunction "2_2") (pintype "passive"))
      (node (ref "JP6") (pin "3") (pinfunction "3_3") (pintype "passive"))
      (node (ref "JP9") (pin "6") (pinfunction "6_6") (pintype "passive"))
      (node (ref "R45") (pin "1") (pinfunction "1_1") (pintype "passive"))
      (node (ref "S1") (pin "1") (pinfunction "1_1") (pintype "passive"))
      (node (ref "S1") (pin "2") (pinfunction "2_2") (pintype "passive"))
      (node (ref "U$1") (pin "10") (pinfunction "GND_10") (pintype "power_in"))
      (node (ref "U$3") (pin "25") (pinfunction "25_25") (pintype "passive"))
      (node (ref "U$4") (pin "10") (pinfunction "10_10") (pintype "passive"))
      (node (ref "U1") (pin "6") (pinfunction "VSS_6") (pintype "power_in"))
      (node (ref "U1") (pin "MT1") (pinfunction "GND_MT1") (pintype "power_in"))
      (node (ref "U1") (pin "MT2") (pinfunction "GND1_MT2") (pintype "power_in"))
      (node (ref "X1") (pin "2") (pinfunction "KL_2") (pintype "passive"))
      (node (ref "X2") (pin "1") (pinfunction "KL_1") (pintype "passive"))
    )
    (net (code "45") (name "N$53") (class "Default")
      (node (ref "JP4") (pin "11") (pinfunction "11_11") (pintype "passive"))
      (node (ref "JP4") (pin "12") (pinfunction "12_12") (pintype "passive"))
    )
    (net (code "46") (name "N$57") (class "Default")
      (node (ref "JP2") (pin "7") (pinfunction "7_7") (pintype "passive"))
      (node (ref "JP2") (pin "8") (pinfunction "8_8") (pintype "passive"))
    )
    (net (code "47") (name "N$58") (class "Default")
      (node (ref "JP2") (pin "10") (pinfunction "10_10") (pintype "passive"))
      (node (ref "JP2") (pin "9") (pinfunction "9_9") (pintype "passive"))
    )
    (net (code "48") (name "Net-(C10-Pad+)") (class "Default")
      (node (ref "C10") (pin "+") (pinfunction "+_+") (pintype "passive"))
      (node (ref "F2") (pin "2") (pinfunction "2_2") (pintype "passive"))
      (node (ref "JP15") (pin "2") (pinfunction "2_2") (pintype "passive"))
    )
    (net (code "49") (name "Net-(CN1-2)") (class "Default")
      (node (ref "CN1") (pin "1") (pinfunction "2_1") (pintype "passive"))
      (node (ref "CN2") (pin "PWR") (pinfunction "PWR_PWR") (pintype "power_in"))
      (node (ref "F1") (pin "1") (pinfunction "1_1") (pintype "passive"))
      (node (ref "SJ1") (pin "2") (pinfunction "2_2") (pintype "passive"))
      (node (ref "X1") (pin "1") (pinfunction "KL_1") (pintype "passive"))
    )
    (net (code "50") (name "Net-(D1-PadC)") (class "Default")
      (node (ref "D1") (pin "C") (pinfunction "C_C") (pintype "passive"))
      (node (ref "F1") (pin "2") (pinfunction "2_2") (pintype "passive"))
      (node (ref "JP10") (pin "2") (pinfunction "2_2") (pintype "passive"))
      (node (ref "SJ1") (pin "1") (pinfunction "1_1") (pintype "passive"))
    )
    (net (code "51") (name "Net-(IC1-VI)") (class "Default")
      (node (ref "C1") (pin "+") (pinfunction "+_+") (pintype "passive"))
      (node (ref "D2") (pin "C") (pinfunction "C_C") (pintype "passive"))
      (node (ref "IC1") (pin "1") (pinfunction "VI_1") (pintype "input"))
      (node (ref "JP10") (pin "1") (pinfunction "1_1") (pintype "passive"))
      (node (ref "SJ2") (pin "2") (pinfunction "2_2") (pintype "passive"))
    )
    (net (code "52") (name "Net-(IC6-A)") (class "Default")
      (node (ref "IC6") (pin "6") (pinfunction "A_6") (pintype "passive"))
      (node (ref "R44") (pin "1") (pinfunction "1_1") (pintype "passive"))
      (node (ref "SJ15") (pin "1") (pinfunction "1_1") (pintype "passive"))
    )
    (net (code "53") (name "Net-(IC6-B)") (class "Default")
      (node (ref "IC6") (pin "7") (pinfunction "B_7") (pintype "passive"))
      (node (ref "R43") (pin "1") (pinfunction "1_1") (pintype "passive"))
      (node (ref "SJ14") (pin "1") (pinfunction "1_1") (pintype "passive"))
    )
    (net (code "54") (name "Net-(IC6-DE)") (class "Default")
      (node (ref "IC6") (pin "3") (pinfunction "DE_3") (pintype "input"))
      (node (ref "JP14") (pin "1") (pinfunction "1_1") (pintype "passive"))
      (node (ref "SJ17") (pin "2") (pinfunction "2_2") (pintype "passive"))
    )
    (net (code "55") (name "Net-(IC6-RE{slash})") (class "Default")
      (node (ref "IC6") (pin "2") (pinfunction "RE/_2") (pintype "input"))
      (node (ref "JP14") (pin "2") (pinfunction "2_2") (pintype "passive"))
      (node (ref "SJ16") (pin "2") (pinfunction "2_2") (pintype "passive"))
    )
    (net (code "56") (name "Net-(JP1-Pad1)") (class "Default")
      (node (ref "JP1") (pin "1") (pinfunction "1_1") (pintype "passive"))
      (node (ref "R9") (pin "2") (pinfunction "2_2") (pintype "passive"))
    )
    (net (code "57") (name "Net-(JP1-Pad2)") (class "Default")
      (node (ref "JP1") (pin "2") (pinfunction "2_2") (pintype "passive"))
      (node (ref "R8") (pin "2") (pinfunction "2_2") (pintype "passive"))
    )
    (net (code "58") (name "Net-(JP1-Pad3)") (class "Default")
      (node (ref "JP1") (pin "3") (pinfunction "3_3") (pintype "passive"))
      (node (ref "R7") (pin "2") (pinfunction "2_2") (pintype "passive"))
    )
    (net (code "59") (name "Net-(JP1-Pad4)") (class "Default")
      (node (ref "JP1") (pin "4") (pinfunction "4_4") (pintype "passive"))
      (node (ref "R6") (pin "2") (pinfunction "2_2") (pintype "passive"))
    )
    (net (code "60") (name "Net-(JP1-Pad5)") (class "Default")
      (node (ref "JP1") (pin "5") (pinfunction "5_5") (pintype "passive"))
      (node (ref "R5") (pin "2") (pinfunction "2_2") (pintype "passive"))
    )
    (net (code "61") (name "Net-(JP1-Pad6)") (class "Default")
      (node (ref "JP1") (pin "6") (pinfunction "6_6") (pintype "passive"))
      (node (ref "R20") (pin "2") (pinfunction "2_2") (pintype "passive"))
    )
    (net (code "62") (name "Net-(JP1-Pad7)") (class "Default")
      (node (ref "JP1") (pin "7") (pinfunction "7_7") (pintype "passive"))
      (node (ref "R19") (pin "2") (pinfunction "2_2") (pintype "passive"))
    )
    (net (code "63") (name "Net-(JP1-Pad8)") (class "Default")
      (node (ref "JP1") (pin "8") (pinfunction "8_8") (pintype "passive"))
      (node (ref "R18") (pin "2") (pinfunction "2_2") (pintype "passive"))
    )
    (net (code "64") (name "Net-(JP1-Pad9)") (class "Default")
      (node (ref "JP1") (pin "9") (pinfunction "9_9") (pintype "passive"))
      (node (ref "R17") (pin "2") (pinfunction "2_2") (pintype "passive"))
    )
    (net (code "65") (name "Net-(JP1-Pad10)") (class "Default")
      (node (ref "JP1") (pin "10") (pinfunction "10_10") (pintype "passive"))
      (node (ref "R16") (pin "2") (pinfunction "2_2") (pintype "passive"))
    )
    (net (code "66") (name "Net-(JP1-Pad11)") (class "Default")
      (node (ref "JP1") (pin "11") (pinfunction "11_11") (pintype "passive"))
      (node (ref "R15") (pin "2") (pinfunction "2_2") (pintype "passive"))
    )
    (net (code "67") (name "Net-(JP1-Pad12)") (class "Default")
      (node (ref "JP1") (pin "12") (pinfunction "12_12") (pintype "passive"))
      (node (ref "R14") (pin "2") (pinfunction "2_2") (pintype "passive"))
    )
    (net (code "68") (name "Net-(JP1-Pad13)") (class "Default")
      (node (ref "JP1") (pin "13") (pinfunction "13_13") (pintype "passive"))
      (node (ref "R13") (pin "2") (pinfunction "2_2") (pintype "passive"))
    )
    (net (code "69") (name "Net-(JP3-Pad1)") (class "Default")
      (node (ref "JP3") (pin "1") (pinfunction "1_1") (pintype "passive"))
      (node (ref "R24") (pin "2") (pinfunction "2_2") (pintype "passive"))
    )
    (net (code "70") (name "Net-(JP3-Pad2)") (class "Default")
      (node (ref "JP3") (pin "2") (pinfunction "2_2") (pintype "passive"))
      (node (ref "R23") (pin "2") (pinfunction "2_2") (pintype "passive"))
    )
    (net (code "71") (name "Net-(JP3-Pad3)") (class "Default")
      (node (ref "JP3") (pin "3") (pinfunction "3_3") (pintype "passive"))
      (node (ref "R22") (pin "2") (pinfunction "2_2") (pintype "passive"))
    )
    (net (code "72") (name "Net-(JP3-Pad4)") (class "Default")
      (node (ref "JP3") (pin "4") (pinfunction "4_4") (pintype "passive"))
      (node (ref "R21") (pin "2") (pinfunction "2_2") (pintype "passive"))
    )
    (net (code "73") (name "Net-(JP3-Pad5)") (class "Default")
      (node (ref "JP3") (pin "5") (pinfunction "5_5") (pintype "passive"))
      (node (ref "R12") (pin "2") (pinfunction "2_2") (pintype "passive"))
    )
    (net (code "74") (name "Net-(JP3-Pad6)") (class "Default")
      (node (ref "JP3") (pin "6") (pinfunction "6_6") (pintype "passive"))
      (node (ref "R11") (pin "2") (pinfunction "2_2") (pintype "passive"))
    )
    (net (code "75") (name "Net-(JP3-Pad7)") (class "Default")
      (node (ref "JP3") (pin "7") (pinfunction "7_7") (pintype "passive"))
      (node (ref "R10") (pin "2") (pinfunction "2_2") (pintype "passive"))
    )
    (net (code "76") (name "Net-(JP3-Pad8)") (class "Default")
      (node (ref "JP3") (pin "8") (pinfunction "8_8") (pintype "passive"))
      (node (ref "R38") (pin "2") (pinfunction "2_2") (pintype "passive"))
    )
    (net (code "77") (name "Net-(JP3-Pad9)") (class "Default")
      (node (ref "JP3") (pin "9") (pinfunction "9_9") (pintype "passive"))
      (node (ref "R37") (pin "2") (pinfunction "2_2") (pintype "passive"))
    )
    (net (code "78") (name "Net-(JP3-Pad10)") (class "Default")
      (node (ref "JP3") (pin "10") (pinfunction "10_10") (pintype "passive"))
      (node (ref "R36") (pin "2") (pinfunction "2_2") (pintype "passive"))
    )
    (net (code "79") (name "Net-(JP3-Pad11)") (class "Default")
      (node (ref "JP3") (pin "11") (pinfunction "11_11") (pintype "passive"))
      (node (ref "R35") (pin "2") (pinfunction "2_2") (pintype "passive"))
    )
    (net (code "80") (name "Net-(JP4-Pad10)") (class "Default")
      (node (ref "JP4") (pin "10") (pinfunction "10_10") (pintype "passive"))
      (node (ref "JP4") (pin "9") (pinfunction "9_9") (pintype "passive"))
      (node (ref "SJ10") (pin "1") (pinfunction "1_1") (pintype "passive"))
      (node (ref "SJ11") (pin "1") (pinfunction "1_1") (pintype "passive"))
      (node (ref "SJ12") (pin "1") (pinfunction "1_1") (pintype "passive"))
      (node (ref "SJ9") (pin "1") (pinfunction "1_1") (pintype "passive"))
    )
    (net (code "81") (name "Net-(JP12-Pad7)") (class "Default")
      (node (ref "JP12") (pin "7") (pinfunction "7_7") (pintype "passive"))
      (node (ref "U$1") (pin "14") (pinfunction "RES_14") (pintype "bidirectional"))
    )
    (net (code "82") (name "Net-(JP13-Pad2)") (class "Default")
      (node (ref "JP13") (pin "2") (pinfunction "2_2") (pintype "passive"))
      (node (ref "U$1") (pin "8") (pinfunction "RES_8") (pintype "bidirectional"))
    )
    (net (code "83") (name "Net-(JP17-Pad1)") (class "Default")
      (node (ref "JP17") (pin "1") (pinfunction "1_1") (pintype "passive"))
      (node (ref "R34") (pin "2") (pinfunction "2_2") (pintype "passive"))
    )
    (net (code "84") (name "Net-(JP17-Pad2)") (class "Default")
      (node (ref "JP17") (pin "2") (pinfunction "2_2") (pintype "passive"))
      (node (ref "R33") (pin "2") (pinfunction "2_2") (pintype "passive"))
    )
    (net (code "85") (name "Net-(JP17-Pad3)") (class "Default")
      (node (ref "JP17") (pin "3") (pinfunction "3_3") (pintype "passive"))
      (node (ref "R32") (pin "2") (pinfunction "2_2") (pintype "passive"))
    )
    (net (code "86") (name "Net-(JP17-Pad4)") (class "Default")
      (node (ref "JP17") (pin "4") (pinfunction "4_4") (pintype "passive"))
      (node (ref "R31") (pin "2") (pinfunction "2_2") (pintype "passive"))
    )
    (net (code "87") (name "Net-(JP17-Pad5)") (class "Default")
      (node (ref "JP17") (pin "5") (pinfunction "5_5") (pintype "passive"))
      (node (ref "R30") (pin "2") (pinfunction "2_2") (pintype "passive"))
    )
    (net (code "88") (name "Net-(JP17-Pad6)") (class "Default")
      (node (ref "JP17") (pin "6") (pinfunction "6_6") (pintype "passive"))
      (node (ref "R29") (pin "2") (pinfunction "2_2") (pintype "passive"))
    )
    (net (code "89") (name "Net-(JP17-Pad7)") (class "Default")
      (node (ref "JP17") (pin "7") (pinfunction "7_7") (pintype "passive"))
      (node (ref "R28") (pin "2") (pinfunction "2_2") (pintype "passive"))
    )
    (net (code "90") (name "Net-(JP17-Pad8)") (class "Default")
      (node (ref "JP17") (pin "8") (pinfunction "8_8") (pintype "passive"))
      (node (ref "R27") (pin "2") (pinfunction "2_2") (pintype "passive"))
    )
    (net (code "91") (name "Net-(JP17-Pad9)") (class "Default")
      (node (ref "JP17") (pin "9") (pinfunction "9_9") (pintype "passive"))
      (node (ref "R26") (pin "2") (pinfunction "2_2") (pintype "passive"))
    )
    (net (code "92") (name "Net-(JP17-Pad10)") (class "Default")
      (node (ref "JP17") (pin "10") (pinfunction "10_10") (pintype "passive"))
      (node (ref "R25") (pin "2") (pinfunction "2_2") (pintype "passive"))
    )
    (net (code "93") (name "Net-(JP18-Pad1)") (class "Default")
      (node (ref "JP18") (pin "1") (pinfunction "1_1") (pintype "passive"))
      (node (ref "R42") (pin "2") (pinfunction "2_2") (pintype "passive"))
    )
    (net (code "94") (name "Net-(JP18-Pad2)") (class "Default")
      (node (ref "JP18") (pin "2") (pinfunction "2_2") (pintype "passive"))
      (node (ref "R41") (pin "2") (pinfunction "2_2") (pintype "passive"))
    )
    (net (code "95") (name "Net-(JP18-Pad3)") (class "Default")
      (node (ref "JP18") (pin "3") (pinfunction "3_3") (pintype "passive"))
      (node (ref "R40") (pin "2") (pinfunction "2_2") (pintype "passive"))
    )
    (net (code "96") (name "Net-(JP18-Pad4)") (class "Default")
      (node (ref "JP18") (pin "4") (pinfunction "4_4") (pintype "passive"))
      (node (ref "R39") (pin "2") (pinfunction "2_2") (pintype "passive"))
    )
    (net (code "97") (name "Net-(U$1-CTS)") (class "Default")
      (node (ref "JP12") (pin "9") (pinfunction "9_9") (pintype "passive"))
      (node (ref "U$1") (pin "12") (pinfunction "CTS_12") (pintype "output"))
    )
    (net (code "98") (name "Net-(U$1-DIO0)") (class "Default")
      (node (ref "JP12") (pin "1") (pinfunction "1_1") (pintype "passive"))
      (node (ref "U$1") (pin "20") (pinfunction "DIO0_20") (pintype "bidirectional"))
    )
    (net (code "99") (name "Net-(U$1-DIO1)") (class "Default")
      (node (ref "JP12") (pin "2") (pinfunction "2_2") (pintype "passive"))
      (node (ref "U$1") (pin "19") (pinfunction "DIO1_19") (pintype "bidirectional"))
    )
    (net (code "100") (name "Net-(U$1-DIO2)") (class "Default")
      (node (ref "JP12") (pin "3") (pinfunction "3_3") (pintype "passive"))
      (node (ref "U$1") (pin "18") (pinfunction "DIO2_18") (pintype "bidirectional"))
    )
    (net (code "101") (name "Net-(U$1-DIO3)") (class "Default")
      (node (ref "JP12") (pin "4") (pinfunction "4_4") (pintype "passive"))
      (node (ref "U$1") (pin "17") (pinfunction "DIO3_17") (pintype "bidirectional"))
    )
    (net (code "102") (name "Net-(U$1-DIO4)") (class "Default")
      (node (ref "JP12") (pin "10") (pinfunction "10_10") (pintype "passive"))
      (node (ref "U$1") (pin "11") (pinfunction "DIO4_11") (pintype "bidirectional"))
    )
    (net (code "103") (name "Net-(U$1-DIO5)") (class "Default")
      (node (ref "JP12") (pin "6") (pinfunction "6_6") (pintype "passive"))
      (node (ref "U$1") (pin "15") (pinfunction "DIO5_15") (pintype "bidirectional"))
    )
    (net (code "104") (name "Net-(U$1-DIO9)") (class "Default")
      (node (ref "JP12") (pin "8") (pinfunction "8_8") (pintype "passive"))
      (node (ref "U$1") (pin "13") (pinfunction "DIO9_13") (pintype "bidirectional"))
    )
    (net (code "105") (name "Net-(U$1-DIO11)") (class "Default")
      (node (ref "JP13") (pin "3") (pinfunction "3_3") (pintype "passive"))
      (node (ref "U$1") (pin "7") (pinfunction "DIO11_7") (pintype "bidirectional"))
    )
    (net (code "106") (name "Net-(U$1-DIO12)") (class "Default")
      (node (ref "JP13") (pin "6") (pinfunction "6_6") (pintype "passive"))
      (node (ref "U$1") (pin "4") (pinfunction "DIO12_4") (pintype "bidirectional"))
    )
    (net (code "107") (name "Net-(U$1-DTR)") (class "Default")
      (node (ref "JP13") (pin "1") (pinfunction "1_1") (pintype "passive"))
      (node (ref "U$1") (pin "9") (pinfunction "DTR_9") (pintype "bidirectional"))
    )
    (net (code "108") (name "Net-(U$1-RESET)") (class "Default")
      (node (ref "JP13") (pin "5") (pinfunction "5_5") (pintype "passive"))
      (node (ref "U$1") (pin "5") (pinfunction "RESET_5") (pintype "input"))
    )
    (net (code "109") (name "Net-(U$1-RSSI)") (class "Default")
      (node (ref "JP13") (pin "4") (pinfunction "4_4") (pintype "passive"))
      (node (ref "U$1") (pin "6") (pinfunction "RSSI_6") (pintype "bidirectional"))
    )
    (net (code "110") (name "Net-(U$1-RTS)") (class "Default")
      (node (ref "JP12") (pin "5") (pinfunction "5_5") (pintype "passive"))
      (node (ref "U$1") (pin "16") (pinfunction "RTS_16") (pintype "input"))
    )
    (net (code "111") (name "Net-(U1-CARD_DETECT)") (class "Default")
      (node (ref "R4") (pin "1") (pinfunction "1_1") (pintype "passive"))
      (node (ref "SJ3") (pin "1") (pinfunction "1_1") (pintype "passive"))
      (node (ref "SJ4") (pin "1") (pinfunction "1_1") (pintype "passive"))
      (node (ref "U1") (pin "CD1") (pinfunction "CARD_DETECT_CD1") (pintype "passive"))
    )
    (net (code "112") (name "Net-(U1-CS)") (class "Default")
      (node (ref "SJ5") (pin "1") (pinfunction "1_1") (pintype "passive"))
      (node (ref "SJ6") (pin "1") (pinfunction "1_1") (pintype "passive"))
      (node (ref "SJ7") (pin "1") (pinfunction "1_1") (pintype "passive"))
      (node (ref "SJ8") (pin "1") (pinfunction "1_1") (pintype "passive"))
      (node (ref "U1") (pin "2") (pinfunction "CS_2") (pintype "input"))
    )
    (net (code "113") (name "Net-(X2B-KL)") (class "Default")
      (node (ref "R44") (pin "2") (pinfunction "2_2") (pintype "passive"))
      (node (ref "R45") (pin "2") (pinfunction "2_2") (pintype "passive"))
      (node (ref "R47") (pin "1") (pinfunction "1_1") (pintype "passive"))
      (node (ref "SJ15") (pin "2") (pinfunction "2_2") (pintype "passive"))
      (node (ref "X2") (pin "2") (pinfunction "KL_2") (pintype "passive"))
    )
    (net (code "114") (name "Net-(X2C-KL)") (class "Default")
      (node (ref "R43") (pin "2") (pinfunction "2_2") (pintype "passive"))
      (node (ref "R46") (pin "1") (pinfunction "1_1") (pintype "passive"))
      (node (ref "R47") (pin "2") (pinfunction "2_2") (pintype "passive"))
      (node (ref "SJ14") (pin "2") (pinfunction "2_2") (pintype "passive"))
      (node (ref "X2") (pin "3") (pinfunction "KL_3") (pintype "passive"))
    )
    (net (code "115") (name "PROG") (class "Default")
      (node (ref "JP11") (pin "3") (pinfunction "3_3") (pintype "passive"))
      (node (ref "JP16") (pin "2") (pinfunction "2_2") (pintype "passive"))
      (node (ref "JP18") (pin "5") (pinfunction "5_5") (pintype "passive"))
      (node (ref "U$4") (pin "6") (pinfunction "6_6") (pintype "passive"))
    )
    (net (code "116") (name "RESET") (class "Default")
      (node (ref "JP11") (pin "1") (pinfunction "1_1") (pintype "passive"))
      (node (ref "JP16") (pin "1") (pinfunction "1_1") (pintype "passive"))
      (node (ref "JP18") (pin "7") (pinfunction "7_7") (pintype "passive"))
      (node (ref "U$4") (pin "8") (pinfunction "8_8") (pintype "passive"))
    )
    (net (code "117") (name "VBAT") (class "Default")
      (node (ref "BAT1") (pin "PWR@1") (pinfunction "+_PWR@1") (pintype "power_in"))
      (node (ref "JP16") (pin "5") (pinfunction "5_5") (pintype "passive"))
      (node (ref "JP18") (pin "10") (pinfunction "10_10") (pintype "passive"))
      (node (ref "U$4") (pin "11") (pinfunction "11_11") (pintype "passive"))
    )
    (net (code "118") (name "VIN") (class "Default")
      (node (ref "JP10") (pin "3") (pinfunction "3_3") (pintype "passive"))
      (node (ref "JP15") (pin "1") (pinfunction "1_1") (pintype "passive"))
      (node (ref "JP3") (pin "14") (pinfunction "14_14") (pintype "passive"))
      (node (ref "JP6") (pin "1") (pinfunction "1_1") (pintype "passive"))
      (node (ref "U$4") (pin "25") (pinfunction "25_25") (pintype "passive"))
    )
    (net (code "119") (name "VUSB") (class "Default")
      (node (ref "C3") (pin "+") (pinfunction "+_+") (pintype "passive"))
      (node (ref "F2") (pin "1") (pinfunction "1_1") (pintype "passive"))
      (node (ref "JP18") (pin "8") (pinfunction "8_8") (pintype "passive"))
      (node (ref "U$4") (pin "9") (pinfunction "9_9") (pintype "passive"))
    )
    (net (code "120") (name "unconnected-(JP6-Pad8)") (class "Default")
      (node (ref "JP6") (pin "8") (pinfunction "8_8") (pintype "passive"))
    )
    (net (code "121") (name "unconnected-(JP9-Pad2)") (class "Default")
      (node (ref "JP9") (pin "2") (pinfunction "2_2") (pintype "passive"))
    )
    (net (code "122") (name "unconnected-(JP9-Pad5)") (class "Default")
      (node (ref "JP9") (pin "5") (pinfunction "5_5") (pintype "passive"))
    )
    (net (code "123") (name "unconnected-(U1-CARD_DETECT1-PadCD2)") (class "Default")
      (node (ref "U1") (pin "CD2") (pinfunction "CARD_DETECT1_CD2") (pintype "passive"))
    )
    (net (code "124") (name "unconnected-(U1-DAT1-Pad8)") (class "Default")
      (node (ref "U1") (pin "8") (pinfunction "DAT1_8") (pintype "bidirectional"))
    )
    (net (code "125") (name "unconnected-(U1-DAT2-Pad1)") (class "Default")
      (node (ref "U1") (pin "1") (pinfunction "DAT2_1") (pintype "bidirectional"))
    )
  )
)
